# lora_receiver.net
KiCad netlist of a schematic drawn in EAGLE
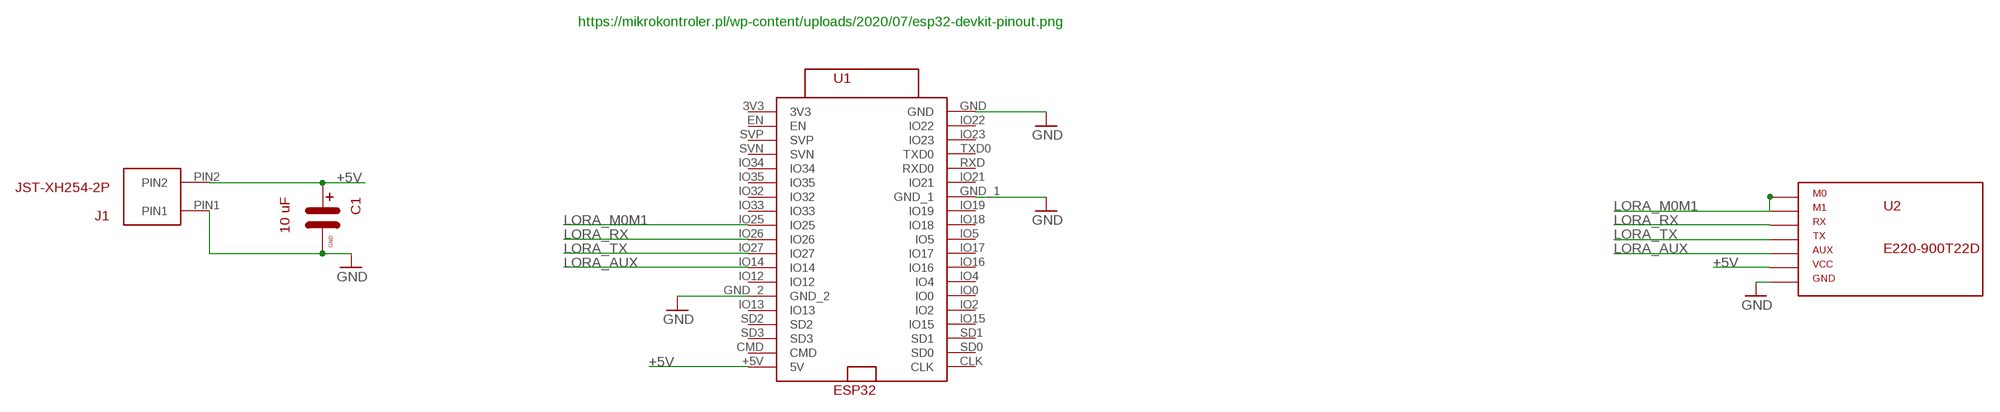
[diagram p0: schematic, sheet 1]

(export (version "E")
  (design (tool "Eeschema 10.0.6"))
  (components
    (comp (ref "C1")
      (value "10 uF")
      (footprint "eagle-import:C-MINI-5X7")
      (libsource (lib "eagle-import") (part "CMINI-5X7"))
    )
    (comp (ref "J1")
      (value "JST-XH254-2P")
      (footprint "eagle-import:JST-XH254-2P")
      (libsource (lib "eagle-import") (part "JST-XH254-2P"))
    )
    (comp (ref "U1")
      (value "ESP32")
      (footprint "eagle-import:ESP32")
      (libsource (lib "eagle-import") (part "ESP32"))
    )
    (comp (ref "U2")
      (value "E220-900T22D")
      (footprint "eagle-import:LORA")
      (libsource (lib "eagle-import") (part "LORA"))
    )
  )
  (nets
    (net (code "1") (name "/+5V") (class "Default")
      (node (ref "C1") (pin "PLUS") (pinfunction "PIN_PLUS_PLUS") (pintype "bidirectional"))
      (node (ref "J1") (pin "PIN2") (pinfunction "PIN2_PIN2") (pintype "bidirectional"))
      (node (ref "U1") (pin "+5V") (pinfunction "5V_+5V") (pintype "power_in"))
      (node (ref "U2") (pin "VCC") (pinfunction "VCC_VCC") (pintype "power_in"))
    )
    (net (code "2") (name "/3V3") (class "Default")
      (node (ref "U1") (pin "3V3") (pinfunction "3V3_3V3") (pintype "power_in"))
    )
    (net (code "3") (name "/LORA_AUX") (class "Default")
      (node (ref "U1") (pin "IO14") (pinfunction "IO14_IO14") (pintype "bidirectional"))
      (node (ref "U2") (pin "AUX") (pinfunction "AUX_AUX") (pintype "bidirectional"))
    )
    (net (code "4") (name "/LORA_M0M1") (class "Default")
      (node (ref "U1") (pin "IO25") (pinfunction "IO25_IO25") (pintype "bidirectional"))
      (node (ref "U2") (pin "M0") (pinfunction "M0_M0") (pintype "bidirectional"))
      (node (ref "U2") (pin "M1") (pinfunction "M1_M1") (pintype "bidirectional"))
    )
    (net (code "5") (name "/LORA_RX") (class "Default")
      (node (ref "U1") (pin "IO26") (pinfunction "IO26_IO26") (pintype "bidirectional"))
      (node (ref "U2") (pin "RX") (pinfunction "RX_RX") (pintype "bidirectional"))
    )
    (net (code "6") (name "/LORA_TX") (class "Default")
      (node (ref "U1") (pin "IO27") (pinfunction "IO27_IO27") (pintype "bidirectional"))
      (node (ref "U2") (pin "TX") (pinfunction "TX_TX") (pintype "bidirectional"))
    )
    (net (code "7") (name "GND") (class "Default")
      (node (ref "C1") (pin "MINUS") (pinfunction "PIN_GND_MINUS") (pintype "bidirectional"))
      (node (ref "J1") (pin "PIN1") (pinfunction "PIN1_PIN1") (pintype "bidirectional"))
      (node (ref "U1") (pin "GND") (pinfunction "GND_GND") (pintype "power_in"))
      (node (ref "U1") (pin "GND_1") (pinfunction "GND_1_GND_1") (pintype "bidirectional"))
      (node (ref "U1") (pin "GND_2") (pinfunction "GND_2_GND_2") (pintype "bidirectional"))
      (node (ref "U2") (pin "GND") (pinfunction "GND_GND") (pintype "power_in"))
    )
    (net (code "8") (name "unconnected-(U1-PadCLK)") (class "Default")
      (node (ref "U1") (pin "CLK") (pinfunction "CLK_CLK") (pintype "bidirectional"))
    )
    (net (code "9") (name "unconnected-(U1-PadCMD)") (class "Default")
      (node (ref "U1") (pin "CMD") (pinfunction "CMD_CMD") (pintype "bidirectional"))
    )
    (net (code "10") (name "unconnected-(U1-PadEN)") (class "Default")
      (node (ref "U1") (pin "EN") (pinfunction "EN_EN") (pintype "bidirectional"))
    )
    (net (code "11") (name "unconnected-(U1-PadIO0)") (class "Default")
      (node (ref "U1") (pin "IO0") (pinfunction "IO0_IO0") (pintype "bidirectional"))
    )
    (net (code "12") (name "unconnected-(U1-PadIO2)") (class "Default")
      (node (ref "U1") (pin "IO2") (pinfunction "IO2_IO2") (pintype "bidirectional"))
    )
    (net (code "13") (name "unconnected-(U1-PadIO4)") (class "Default")
      (node (ref "U1") (pin "IO4") (pinfunction "IO4_IO4") (pintype "bidirectional"))
    )
    (net (code "14") (name "unconnected-(U1-PadIO5)") (class "Default")
      (node (ref "U1") (pin "IO5") (pinfunction "IO5_IO5") (pintype "bidirectional"))
    )
    (net (code "15") (name "unconnected-(U1-PadIO12)") (class "Default")
      (node (ref "U1") (pin "IO12") (pinfunction "IO12_IO12") (pintype "bidirectional"))
    )
    (net (code "16") (name "unconnected-(U1-PadIO13)") (class "Default")
      (node (ref "U1") (pin "IO13") (pinfunction "IO13_IO13") (pintype "bidirectional"))
    )
    (net (code "17") (name "unconnected-(U1-PadIO15)") (class "Default")
      (node (ref "U1") (pin "IO15") (pinfunction "IO15_IO15") (pintype "bidirectional"))
    )
    (net (code "18") (name "unconnected-(U1-PadIO16)") (class "Default")
      (node (ref "U1") (pin "IO16") (pinfunction "IO16_IO16") (pintype "bidirectional"))
    )
    (net (code "19") (name "unconnected-(U1-PadIO17)") (class "Default")
      (node (ref "U1") (pin "IO17") (pinfunction "IO17_IO17") (pintype "bidirectional"))
    )
    (net (code "20") (name "unconnected-(U1-PadIO18)") (class "Default")
      (node (ref "U1") (pin "IO18") (pinfunction "IO18_IO18") (pintype "bidirectional"))
    )
    (net (code "21") (name "unconnected-(U1-PadIO19)") (class "Default")
      (node (ref "U1") (pin "IO19") (pinfunction "IO19_IO19") (pintype "bidirectional"))
    )
    (net (code "22") (name "unconnected-(U1-PadIO21)") (class "Default")
      (node (ref "U1") (pin "IO21") (pinfunction "IO21_IO21") (pintype "bidirectional"))
    )
    (net (code "23") (name "unconnected-(U1-PadIO22)") (class "Default")
      (node (ref "U1") (pin "IO22") (pinfunction "IO22_IO22") (pintype "bidirectional"))
    )
    (net (code "24") (name "unconnected-(U1-PadIO23)") (class "Default")
      (node (ref "U1") (pin "IO23") (pinfunction "IO23_IO23") (pintype "bidirectional"))
    )
    (net (code "25") (name "unconnected-(U1-PadIO32)") (class "Default")
      (node (ref "U1") (pin "IO32") (pinfunction "IO32_IO32") (pintype "bidirectional"))
    )
    (net (code "26") (name "unconnected-(U1-PadIO33)") (class "Default")
      (node (ref "U1") (pin "IO33") (pinfunction "IO33_IO33") (pintype "bidirectional"))
    )
    (net (code "27") (name "unconnected-(U1-PadIO34)") (class "Default")
      (node (ref "U1") (pin "IO34") (pinfunction "IO34_IO34") (pintype "bidirectional"))
    )
    (net (code "28") (name "unconnected-(U1-PadIO35)") (class "Default")
      (node (ref "U1") (pin "IO35") (pinfunction "IO35_IO35") (pintype "bidirectional"))
    )
    (net (code "29") (name "unconnected-(U1-PadSD0)") (class "Default")
      (node (ref "U1") (pin "SD0") (pinfunction "SD0_SD0") (pintype "bidirectional"))
    )
    (net (code "30") (name "unconnected-(U1-PadSD1)") (class "Default")
      (node (ref "U1") (pin "SD1") (pinfunction "SD1_SD1") (pintype "bidirectional"))
    )
    (net (code "31") (name "unconnected-(U1-PadSD2)") (class "Default")
      (node (ref "U1") (pin "SD2") (pinfunction "SD2_SD2") (pintype "bidirectional"))
    )
    (net (code "32") (name "unconnected-(U1-PadSD3)") (class "Default")
      (node (ref "U1") (pin "SD3") (pinfunction "SD3_SD3") (pintype "bidirectional"))
    )
    (net (code "33") (name "unconnected-(U1-PadSVN)") (class "Default")
      (node (ref "U1") (pin "SVN") (pinfunction "SVN_SVN") (pintype "bidirectional"))
    )
    (net (code "34") (name "unconnected-(U1-PadSVP)") (class "Default")
      (node (ref "U1") (pin "SVP") (pinfunction "SVP_SVP") (pintype "bidirectional"))
    )
    (net (code "35") (name "unconnected-(U1-PadTXD0)") (class "Default")
      (node (ref "U1") (pin "TXD0") (pinfunction "TXD0_TXD0") (pintype "bidirectional"))
    )
    (net (code "36") (name "unconnected-(U1-RXD0-PadRXD)") (class "Default")
      (node (ref "U1") (pin "RXD") (pinfunction "RXD0_RXD") (pintype "bidirectional"))
    )
  )
)
